# final_proj_board.net
KiCad netlist of a schematic drawn in EAGLE
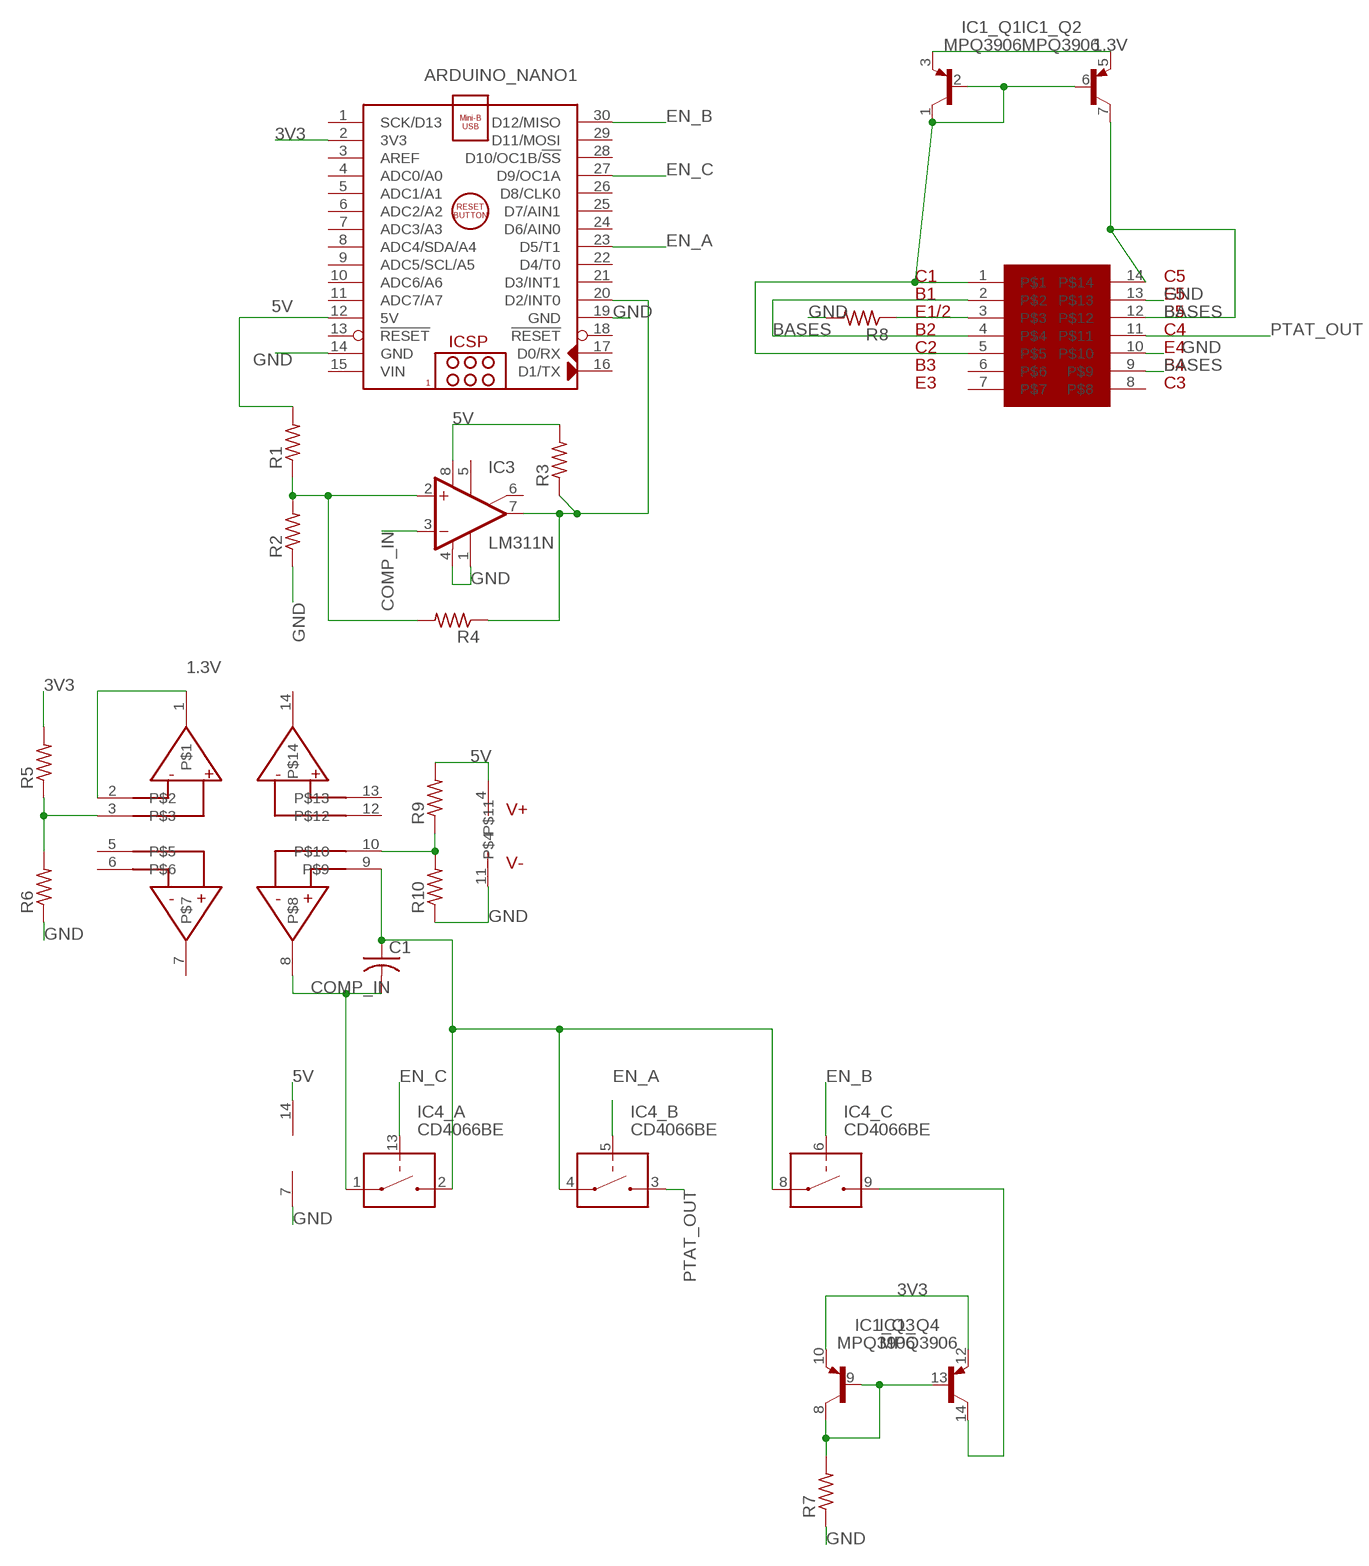
[diagram p0: schematic, sheet 1]

(export (version "E")
  (design (tool "Eeschema 10.0.6"))
  (components
    (comp (ref "ARDUINO_NANO1")
      (value "ARDUINO_NANO")
      (footprint "eagle-import:ARDUINO_NANO")
      (libsource (lib "eagle-import") (part "ARDUINO_NANO"))
    )
    (comp (ref "C1")
      (value "C-US050-024X044")
      (footprint "eagle-import:C050-024X044")
      (libsource (lib "eagle-import") (part "C-US050-024X044"))
    )
    (comp (ref "IC1")
      (value "MPQ3906")
      (footprint "eagle-import:DIL14")
      (libsource (lib "eagle-import") (part "MPQ3906"))
    )
    (comp (ref "IC2")
      (value "CA3046")
      (footprint "eagle-import:DIL14")
      (libsource (lib "eagle-import") (part "CA3046"))
    )
    (comp (ref "IC3")
      (value "LM311N")
      (footprint "eagle-import:DIL08")
      (libsource (lib "eagle-import") (part "LM311N"))
    )
    (comp (ref "IC4")
      (value "CD4066BE")
      (footprint "eagle-import:DIL14")
      (libsource (lib "eagle-import") (part "CD4066BE"))
    )
    (comp (ref "R1")
      (value "R-US_0204/7")
      (footprint "eagle-import:0204_7")
      (libsource (lib "eagle-import") (part "R-US_0204/7"))
    )
    (comp (ref "R2")
      (value "R-US_0204/7")
      (footprint "eagle-import:0204_7")
      (libsource (lib "eagle-import") (part "R-US_0204/7"))
    )
    (comp (ref "R3")
      (value "R-US_0204/7")
      (footprint "eagle-import:0204_7")
      (libsource (lib "eagle-import") (part "R-US_0204/7"))
    )
    (comp (ref "R4")
      (value "R-US_0204/7")
      (footprint "eagle-import:0204_7")
      (libsource (lib "eagle-import") (part "R-US_0204/7"))
    )
    (comp (ref "R5")
      (value "R-US_0204/7")
      (footprint "eagle-import:0204_7")
      (libsource (lib "eagle-import") (part "R-US_0204/7"))
    )
    (comp (ref "R6")
      (value "R-US_0204/7")
      (footprint "eagle-import:0204_7")
      (libsource (lib "eagle-import") (part "R-US_0204/7"))
    )
    (comp (ref "R7")
      (value "R-US_0204/7")
      (footprint "eagle-import:0204_7")
      (libsource (lib "eagle-import") (part "R-US_0204/7"))
    )
    (comp (ref "R8")
      (value "R-US_0204/7")
      (footprint "eagle-import:0204_7")
      (libsource (lib "eagle-import") (part "R-US_0204/7"))
    )
    (comp (ref "R9")
      (value "R-US_0204/7")
      (footprint "eagle-import:0204_7")
      (libsource (lib "eagle-import") (part "R-US_0204/7"))
    )
    (comp (ref "R10")
      (value "R-US_0204/7")
      (footprint "eagle-import:0204_7")
      (libsource (lib "eagle-import") (part "R-US_0204/7"))
    )
    (comp (ref "U$1")
      (value "LM6134")
      (footprint "eagle-import:DIL14")
      (libsource (lib "eagle-import") (part "LM6134"))
    )
  )
  (nets
    (net (code "1") (name "/1.3V") (class "Default")
      (node (ref "IC1") (pin "3") (pinfunction "E_3") (pintype "passive"))
      (node (ref "IC1") (pin "5") (pinfunction "E_5") (pintype "passive"))
      (node (ref "U$1") (pin "1") (pinfunction "P$1_1") (pintype "bidirectional"))
      (node (ref "U$1") (pin "2") (pinfunction "P$2_2") (pintype "bidirectional"))
    )
    (net (code "2") (name "/3V3") (class "Default")
      (node (ref "ARDUINO_NANO1") (pin "2") (pinfunction "3V3_2") (pintype "output"))
      (node (ref "IC1") (pin "10") (pinfunction "E_10") (pintype "passive"))
      (node (ref "IC1") (pin "12") (pinfunction "E_12") (pintype "passive"))
      (node (ref "R5") (pin "2") (pinfunction "2_2") (pintype "passive"))
    )
    (net (code "3") (name "/5V") (class "Default")
      (node (ref "ARDUINO_NANO1") (pin "12") (pinfunction "5V_12") (pintype "power_in"))
      (node (ref "IC3") (pin "8") (pinfunction "V+_8") (pintype "power_in"))
      (node (ref "IC4") (pin "14") (pinfunction "V+_14") (pintype "power_in"))
      (node (ref "R1") (pin "2") (pinfunction "2_2") (pintype "passive"))
      (node (ref "R3") (pin "2") (pinfunction "2_2") (pintype "passive"))
      (node (ref "R9") (pin "2") (pinfunction "2_2") (pintype "passive"))
      (node (ref "U$1") (pin "4") (pinfunction "P$4_4") (pintype "bidirectional"))
    )
    (net (code "4") (name "/BASES") (class "Default")
      (node (ref "IC1") (pin "7") (pinfunction "C_7") (pintype "passive"))
      (node (ref "IC2") (pin "12") (pinfunction "P$12_12") (pintype "bidirectional"))
      (node (ref "IC2") (pin "14") (pinfunction "P$14_14") (pintype "bidirectional"))
      (node (ref "IC2") (pin "2") (pinfunction "P$2_2") (pintype "bidirectional"))
      (node (ref "IC2") (pin "4") (pinfunction "P$4_4") (pintype "bidirectional"))
      (node (ref "IC2") (pin "9") (pinfunction "P$9_9") (pintype "bidirectional"))
    )
    (net (code "5") (name "/COMP_IN") (class "Default")
      (node (ref "C1") (pin "2") (pinfunction "2_2") (pintype "passive"))
      (node (ref "IC3") (pin "3") (pinfunction "-IN_3") (pintype "input"))
      (node (ref "IC4") (pin "1") (pinfunction "IN/OUT1_1") (pintype "bidirectional"))
      (node (ref "U$1") (pin "8") (pinfunction "P$8_8") (pintype "bidirectional"))
    )
    (net (code "6") (name "/EN_A") (class "Default")
      (node (ref "ARDUINO_NANO1") (pin "23") (pinfunction "D5/T1_23") (pintype "bidirectional"))
      (node (ref "IC4") (pin "5") (pinfunction "CONTROL_5") (pintype "bidirectional"))
    )
    (net (code "7") (name "/EN_B") (class "Default")
      (node (ref "ARDUINO_NANO1") (pin "30") (pinfunction "D12/MISO_30") (pintype "bidirectional"))
      (node (ref "IC4") (pin "6") (pinfunction "CONTROL_6") (pintype "bidirectional"))
    )
    (net (code "8") (name "/EN_C") (class "Default")
      (node (ref "ARDUINO_NANO1") (pin "27") (pinfunction "D9/OC1A_27") (pintype "bidirectional"))
      (node (ref "IC4") (pin "13") (pinfunction "CONTROL_13") (pintype "bidirectional"))
    )
    (net (code "9") (name "/GND") (class "Default")
      (node (ref "ARDUINO_NANO1") (pin "14") (pinfunction "GND_14") (pintype "power_in"))
      (node (ref "ARDUINO_NANO1") (pin "19") (pinfunction "GND_19") (pintype "power_in"))
      (node (ref "IC2") (pin "10") (pinfunction "P$10_10") (pintype "bidirectional"))
      (node (ref "IC2") (pin "13") (pinfunction "P$13_13") (pintype "bidirectional"))
      (node (ref "IC3") (pin "1") (pinfunction "GND_1") (pintype "passive"))
      (node (ref "IC3") (pin "4") (pinfunction "V-_4") (pintype "power_in"))
      (node (ref "IC4") (pin "7") (pinfunction "V-_7") (pintype "power_in"))
      (node (ref "R10") (pin "1") (pinfunction "1_1") (pintype "passive"))
      (node (ref "R2") (pin "1") (pinfunction "1_1") (pintype "passive"))
      (node (ref "R6") (pin "1") (pinfunction "1_1") (pintype "passive"))
      (node (ref "R7") (pin "1") (pinfunction "1_1") (pintype "passive"))
      (node (ref "R8") (pin "2") (pinfunction "2_2") (pintype "passive"))
      (node (ref "U$1") (pin "11") (pinfunction "P$11_11") (pintype "bidirectional"))
    )
    (net (code "10") (name "/PTAT_OUT") (class "Default")
      (node (ref "IC2") (pin "11") (pinfunction "P$11_11") (pintype "bidirectional"))
      (node (ref "IC4") (pin "3") (pinfunction "IN/OUT2_3") (pintype "bidirectional"))
    )
    (net (code "11") (name "/VIN") (class "Default")
      (node (ref "ARDUINO_NANO1") (pin "15") (pinfunction "VIN_15") (pintype "power_in"))
    )
    (net (code "12") (name "Net-(ARDUINO_NANO1-D2{slash}INT0)") (class "Default")
      (node (ref "ARDUINO_NANO1") (pin "20") (pinfunction "D2/INT0_20") (pintype "bidirectional"))
      (node (ref "IC3") (pin "7") (pinfunction "OUT_7") (pintype "output"))
      (node (ref "R3") (pin "1") (pinfunction "1_1") (pintype "passive"))
      (node (ref "R4") (pin "1") (pinfunction "1_1") (pintype "passive"))
    )
    (net (code "13") (name "Net-(IC1A-B)") (class "Default")
      (node (ref "IC1") (pin "1") (pinfunction "C_1") (pintype "passive"))
      (node (ref "IC1") (pin "2") (pinfunction "B_2") (pintype "passive"))
      (node (ref "IC1") (pin "6") (pinfunction "B_6") (pintype "passive"))
      (node (ref "IC2") (pin "1") (pinfunction "P$1_1") (pintype "bidirectional"))
      (node (ref "IC2") (pin "5") (pinfunction "P$5_5") (pintype "bidirectional"))
    )
    (net (code "14") (name "Net-(IC1C-B)") (class "Default")
      (node (ref "IC1") (pin "13") (pinfunction "B_13") (pintype "passive"))
      (node (ref "IC1") (pin "8") (pinfunction "C_8") (pintype "passive"))
      (node (ref "IC1") (pin "9") (pinfunction "B_9") (pintype "passive"))
      (node (ref "R7") (pin "2") (pinfunction "2_2") (pintype "passive"))
    )
    (net (code "15") (name "Net-(IC1D-C)") (class "Default")
      (node (ref "IC1") (pin "14") (pinfunction "C_14") (pintype "passive"))
      (node (ref "IC4") (pin "9") (pinfunction "IN/OUT2_9") (pintype "bidirectional"))
    )
    (net (code "16") (name "Net-(IC2-P$3)") (class "Default")
      (node (ref "IC2") (pin "3") (pinfunction "P$3_3") (pintype "bidirectional"))
      (node (ref "R8") (pin "1") (pinfunction "1_1") (pintype "passive"))
    )
    (net (code "17") (name "Net-(IC3-+IN)") (class "Default")
      (node (ref "IC3") (pin "2") (pinfunction "+IN_2") (pintype "input"))
      (node (ref "R1") (pin "1") (pinfunction "1_1") (pintype "passive"))
      (node (ref "R2") (pin "2") (pinfunction "2_2") (pintype "passive"))
      (node (ref "R4") (pin "2") (pinfunction "2_2") (pintype "passive"))
    )
    (net (code "18") (name "Net-(IC4B-IN{slash}OUT2)") (class "Default")
      (node (ref "C1") (pin "1") (pinfunction "1_1") (pintype "passive"))
      (node (ref "IC4") (pin "2") (pinfunction "IN/OUT2_2") (pintype "bidirectional"))
      (node (ref "IC4") (pin "4") (pinfunction "IN/OUT1_4") (pintype "bidirectional"))
      (node (ref "IC4") (pin "8") (pinfunction "IN/OUT1_8") (pintype "bidirectional"))
      (node (ref "U$1") (pin "9") (pinfunction "P$9_9") (pintype "bidirectional"))
    )
    (net (code "19") (name "Net-(U$1-P$3)") (class "Default")
      (node (ref "R5") (pin "1") (pinfunction "1_1") (pintype "passive"))
      (node (ref "R6") (pin "2") (pinfunction "2_2") (pintype "passive"))
      (node (ref "U$1") (pin "3") (pinfunction "P$3_3") (pintype "bidirectional"))
    )
    (net (code "20") (name "Net-(U$1-P$10)") (class "Default")
      (node (ref "R10") (pin "2") (pinfunction "2_2") (pintype "passive"))
      (node (ref "R9") (pin "1") (pinfunction "1_1") (pintype "passive"))
      (node (ref "U$1") (pin "10") (pinfunction "P$10_10") (pintype "bidirectional"))
    )
    (net (code "21") (name "unconnected-(ARDUINO_NANO1-ADC0{slash}A0-Pad4)") (class "Default")
      (node (ref "ARDUINO_NANO1") (pin "4") (pinfunction "ADC0/A0_4") (pintype "bidirectional"))
    )
    (net (code "22") (name "unconnected-(ARDUINO_NANO1-ADC1{slash}A1-Pad5)") (class "Default")
      (node (ref "ARDUINO_NANO1") (pin "5") (pinfunction "ADC1/A1_5") (pintype "bidirectional"))
    )
    (net (code "23") (name "unconnected-(ARDUINO_NANO1-ADC2{slash}A2-Pad6)") (class "Default")
      (node (ref "ARDUINO_NANO1") (pin "6") (pinfunction "ADC2/A2_6") (pintype "bidirectional"))
    )
    (net (code "24") (name "unconnected-(ARDUINO_NANO1-ADC3{slash}A3-Pad7)") (class "Default")
      (node (ref "ARDUINO_NANO1") (pin "7") (pinfunction "ADC3/A3_7") (pintype "bidirectional"))
    )
    (net (code "25") (name "unconnected-(ARDUINO_NANO1-ADC4{slash}SDA{slash}A4-Pad8)") (class "Default")
      (node (ref "ARDUINO_NANO1") (pin "8") (pinfunction "ADC4/SDA/A4_8") (pintype "bidirectional"))
    )
    (net (code "26") (name "unconnected-(ARDUINO_NANO1-ADC5{slash}SCL{slash}A5-Pad9)") (class "Default")
      (node (ref "ARDUINO_NANO1") (pin "9") (pinfunction "ADC5/SCL/A5_9") (pintype "bidirectional"))
    )
    (net (code "27") (name "unconnected-(ARDUINO_NANO1-ADC6{slash}A6-Pad10)") (class "Default")
      (node (ref "ARDUINO_NANO1") (pin "10") (pinfunction "ADC6/A6_10") (pintype "bidirectional"))
    )
    (net (code "28") (name "unconnected-(ARDUINO_NANO1-ADC7{slash}A7-Pad11)") (class "Default")
      (node (ref "ARDUINO_NANO1") (pin "11") (pinfunction "ADC7/A7_11") (pintype "bidirectional"))
    )
    (net (code "29") (name "unconnected-(ARDUINO_NANO1-AREF-Pad3)") (class "Default")
      (node (ref "ARDUINO_NANO1") (pin "3") (pinfunction "AREF_3") (pintype "input"))
    )
    (net (code "30") (name "unconnected-(ARDUINO_NANO1-D0{slash}RX-Pad17)") (class "Default")
      (node (ref "ARDUINO_NANO1") (pin "17") (pinfunction "D0/RX_17") (pintype "bidirectional"))
    )
    (net (code "31") (name "unconnected-(ARDUINO_NANO1-D1{slash}TX-Pad16)") (class "Default")
      (node (ref "ARDUINO_NANO1") (pin "16") (pinfunction "D1/TX_16") (pintype "bidirectional"))
    )
    (net (code "32") (name "unconnected-(ARDUINO_NANO1-D3{slash}INT1-Pad21)") (class "Default")
      (node (ref "ARDUINO_NANO1") (pin "21") (pinfunction "D3/INT1_21") (pintype "bidirectional"))
    )
    (net (code "33") (name "unconnected-(ARDUINO_NANO1-D4{slash}T0-Pad22)") (class "Default")
      (node (ref "ARDUINO_NANO1") (pin "22") (pinfunction "D4/T0_22") (pintype "bidirectional"))
    )
    (net (code "34") (name "unconnected-(ARDUINO_NANO1-D6{slash}AIN0-Pad24)") (class "Default")
      (node (ref "ARDUINO_NANO1") (pin "24") (pinfunction "D6/AIN0_24") (pintype "bidirectional"))
    )
    (net (code "35") (name "unconnected-(ARDUINO_NANO1-D7{slash}AIN1-Pad25)") (class "Default")
      (node (ref "ARDUINO_NANO1") (pin "25") (pinfunction "D7/AIN1_25") (pintype "bidirectional"))
    )
    (net (code "36") (name "unconnected-(ARDUINO_NANO1-D8{slash}CLK0-Pad26)") (class "Default")
      (node (ref "ARDUINO_NANO1") (pin "26") (pinfunction "D8/CLK0_26") (pintype "bidirectional"))
    )
    (net (code "37") (name "unconnected-(ARDUINO_NANO1-D10{slash}OC1B{slash}~{SS}-Pad28)") (class "Default")
      (node (ref "ARDUINO_NANO1") (pin "28") (pinfunction "D10/OC1B/~{SS}_28") (pintype "bidirectional"))
    )
    (net (code "38") (name "unconnected-(ARDUINO_NANO1-D11{slash}MOSI-Pad29)") (class "Default")
      (node (ref "ARDUINO_NANO1") (pin "29") (pinfunction "D11/MOSI_29") (pintype "bidirectional"))
    )
    (net (code "39") (name "unconnected-(ARDUINO_NANO1-SCK{slash}D13-Pad1)") (class "Default")
      (node (ref "ARDUINO_NANO1") (pin "1") (pinfunction "SCK/D13_1") (pintype "bidirectional"))
    )
    (net (code "40") (name "unconnected-(ARDUINO_NANO1-~{RESET}-Pad13)") (class "Default")
      (node (ref "ARDUINO_NANO1") (pin "13") (pinfunction "~{RESET}_13") (pintype "input"))
    )
    (net (code "41") (name "unconnected-(ARDUINO_NANO1-~{RESET}-Pad18)") (class "Default")
      (node (ref "ARDUINO_NANO1") (pin "18") (pinfunction "~{RESET}_18") (pintype "input"))
    )
    (net (code "42") (name "unconnected-(IC2-P$6-Pad6)") (class "Default")
      (node (ref "IC2") (pin "6") (pinfunction "P$6_6") (pintype "bidirectional"))
    )
    (net (code "43") (name "unconnected-(IC2-P$7-Pad7)") (class "Default")
      (node (ref "IC2") (pin "7") (pinfunction "P$7_7") (pintype "bidirectional"))
    )
    (net (code "44") (name "unconnected-(IC2-P$8-Pad8)") (class "Default")
      (node (ref "IC2") (pin "8") (pinfunction "P$8_8") (pintype "bidirectional"))
    )
    (net (code "45") (name "unconnected-(IC3-ON-Pad5)") (class "Default")
      (node (ref "IC3") (pin "5") (pinfunction "ON_5") (pintype "passive"))
    )
    (net (code "46") (name "unconnected-(IC3-ON{slash}STR-Pad6)") (class "Default")
      (node (ref "IC3") (pin "6") (pinfunction "ON/STR_6") (pintype "passive"))
    )
    (net (code "47") (name "unconnected-(U$1-P$5-Pad5)") (class "Default")
      (node (ref "U$1") (pin "5") (pinfunction "P$5_5") (pintype "bidirectional"))
    )
    (net (code "48") (name "unconnected-(U$1-P$6-Pad6)") (class "Default")
      (node (ref "U$1") (pin "6") (pinfunction "P$6_6") (pintype "bidirectional"))
    )
    (net (code "49") (name "unconnected-(U$1-P$7-Pad7)") (class "Default")
      (node (ref "U$1") (pin "7") (pinfunction "P$7_7") (pintype "bidirectional"))
    )
    (net (code "50") (name "unconnected-(U$1-P$12-Pad12)") (class "Default")
      (node (ref "U$1") (pin "12") (pinfunction "P$12_12") (pintype "bidirectional"))
    )
    (net (code "51") (name "unconnected-(U$1-P$13-Pad13)") (class "Default")
      (node (ref "U$1") (pin "13") (pinfunction "P$13_13") (pintype "bidirectional"))
    )
    (net (code "52") (name "unconnected-(U$1-P$14-Pad14)") (class "Default")
      (node (ref "U$1") (pin "14") (pinfunction "P$14_14") (pintype "bidirectional"))
    )
  )
)
